# PCB_with_nRF_SINGLE.net
KiCad netlist of a schematic drawn in EAGLE
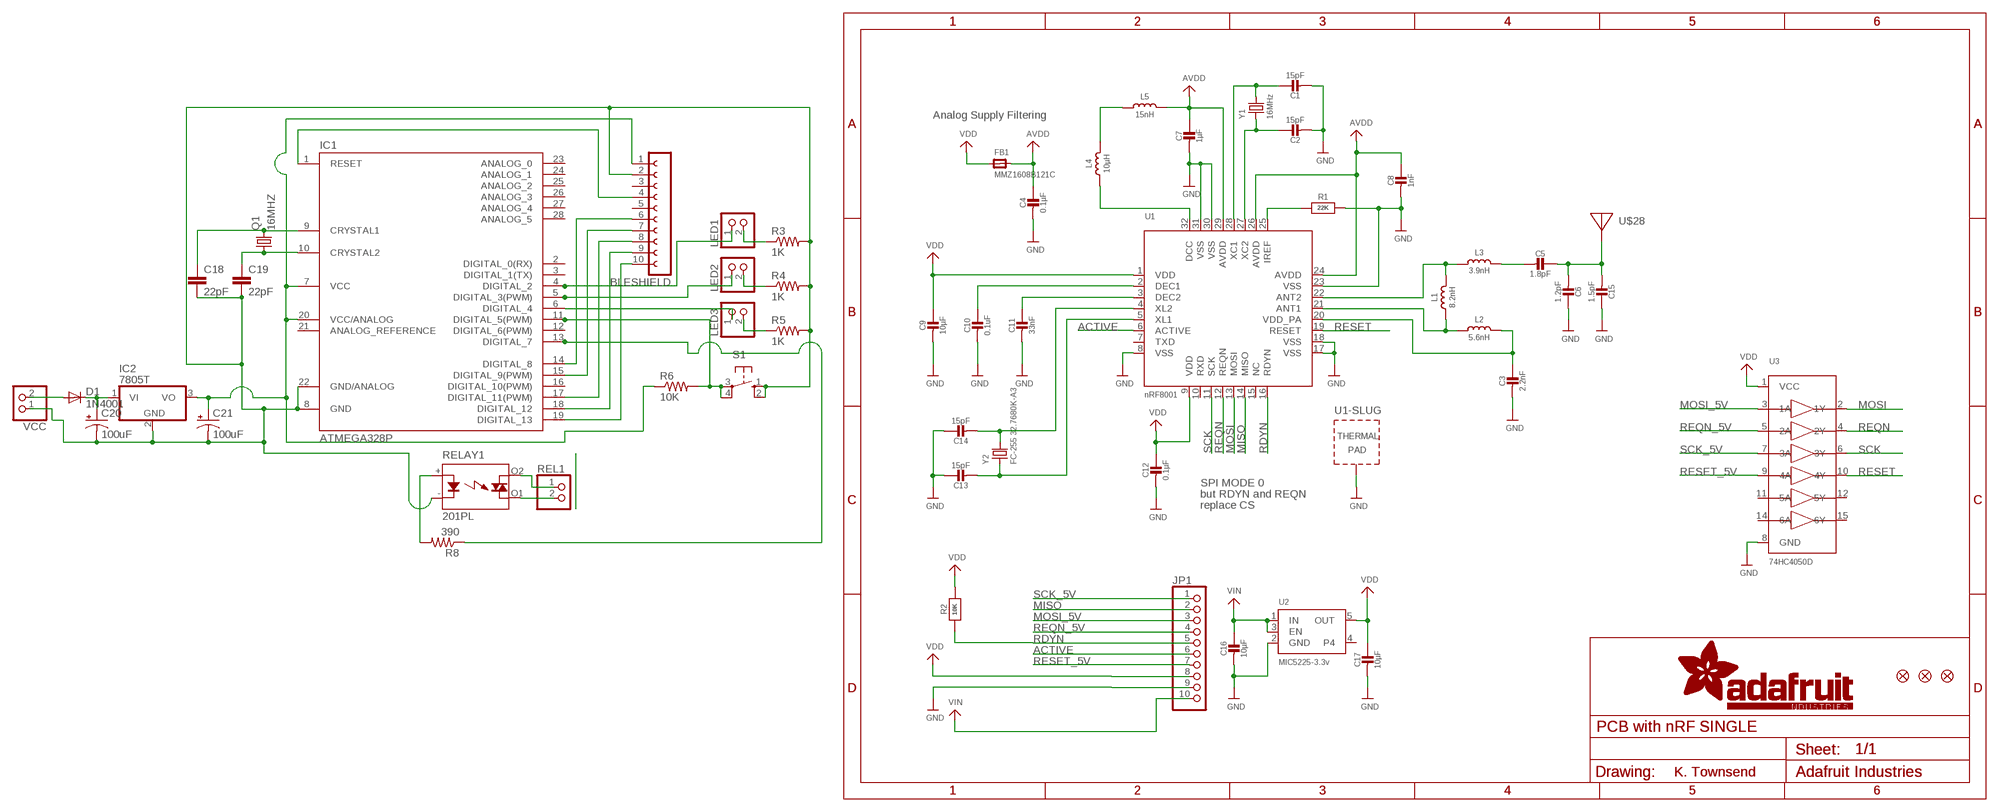
[diagram p0: schematic, sheet 1]

(export (version "E")
  (design (tool "Eeschema 10.0.6"))
  (components
    (comp (ref "BLESHIELD")
      (value "FE10-1")
      (footprint "eagle-import:FE10")
      (libsource (lib "eagle-import") (part "FE10-1"))
    )
    (comp (ref "C1")
      (value "15pF")
      (footprint "eagle-import:0805-NO")
      (libsource (lib "eagle-import") (part "CAP_CERAMIC0805-NOOUTLINE"))
    )
    (comp (ref "C2")
      (value "15pF")
      (footprint "eagle-import:0805-NO")
      (libsource (lib "eagle-import") (part "CAP_CERAMIC0805-NOOUTLINE"))
    )
    (comp (ref "C3")
      (value "2.2nF")
      (footprint "eagle-import:_0402")
      (libsource (lib "eagle-import") (part "CAP_CERAMIC_0402"))
    )
    (comp (ref "C4")
      (value "0.1µF")
      (footprint "eagle-import:0805-NO")
      (libsource (lib "eagle-import") (part "CAP_CERAMIC0805-NOOUTLINE"))
    )
    (comp (ref "C5")
      (value "1.8pF")
      (footprint "eagle-import:_0402MP")
      (libsource (lib "eagle-import") (part "CAP_CERAMIC_0402MP"))
    )
    (comp (ref "C6")
      (value "1.2pF")
      (footprint "eagle-import:_0402MP")
      (libsource (lib "eagle-import") (part "CAP_CERAMIC_0402MP"))
    )
    (comp (ref "C7")
      (value "1µF")
      (footprint "eagle-import:0805-NO")
      (libsource (lib "eagle-import") (part "CAP_CERAMIC0805-NOOUTLINE"))
    )
    (comp (ref "C8")
      (value "1nF")
      (footprint "eagle-import:_0603")
      (libsource (lib "eagle-import") (part "CAP_CERAMIC_0603"))
    )
    (comp (ref "C9")
      (value "10µF")
      (footprint "eagle-import:0805-NO")
      (libsource (lib "eagle-import") (part "CAP_CERAMIC0805-NOOUTLINE"))
    )
    (comp (ref "C10")
      (value "0.1uF")
      (footprint "eagle-import:0805-NO")
      (libsource (lib "eagle-import") (part "CAP_CERAMIC0805-NOOUTLINE"))
    )
    (comp (ref "C11")
      (value "33nF")
      (footprint "eagle-import:0805-NO")
      (libsource (lib "eagle-import") (part "CAP_CERAMIC0805-NOOUTLINE"))
    )
    (comp (ref "C12")
      (value "0.1µF")
      (footprint "eagle-import:0805-NO")
      (libsource (lib "eagle-import") (part "CAP_CERAMIC0805-NOOUTLINE"))
    )
    (comp (ref "C13")
      (value "15pF")
      (footprint "eagle-import:0805-NO")
      (libsource (lib "eagle-import") (part "CAP_CERAMIC0805-NOOUTLINE"))
    )
    (comp (ref "C14")
      (value "15pF")
      (footprint "eagle-import:0805-NO")
      (libsource (lib "eagle-import") (part "CAP_CERAMIC0805-NOOUTLINE"))
    )
    (comp (ref "C15")
      (value "1.5pF")
      (footprint "eagle-import:_0402MP")
      (libsource (lib "eagle-import") (part "CAP_CERAMIC_0402MP"))
    )
    (comp (ref "C16")
      (value "10µF")
      (footprint "eagle-import:0805-NO")
      (libsource (lib "eagle-import") (part "CAP_CERAMIC0805-NOOUTLINE"))
    )
    (comp (ref "C17")
      (value "10µF")
      (footprint "eagle-import:0805-NO")
      (libsource (lib "eagle-import") (part "CAP_CERAMIC0805-NOOUTLINE"))
    )
    (comp (ref "C18")
      (value "22pF")
      (footprint "eagle-import:C025-030X050")
      (libsource (lib "eagle-import") (part "C-EU025-030X050"))
    )
    (comp (ref "C19")
      (value "22pF")
      (footprint "eagle-import:C025-030X050")
      (libsource (lib "eagle-import") (part "C-EU025-030X050"))
    )
    (comp (ref "C20")
      (value "100uF")
      (footprint "eagle-import:E2,5-6")
      (libsource (lib "eagle-import") (part "CPOL-USE2.5-6"))
    )
    (comp (ref "C21")
      (value "100uF")
      (footprint "eagle-import:E2,5-6")
      (libsource (lib "eagle-import") (part "CPOL-USE2.5-6"))
    )
    (comp (ref "D1")
      (value "1N4001")
      (footprint "eagle-import:DO41-10")
      (libsource (lib "eagle-import") (part "1N4004"))
    )
    (comp (ref "FB1")
      (value "MMZ1608B121C")
      (footprint "eagle-import:0805")
      (libsource (lib "eagle-import") (part "FERRITE0805"))
    )
    (comp (ref "FID1")
      (value "FIDUCIAL\"\"")
      (footprint "eagle-import:FIDUCIAL_1MM")
      (libsource (lib "eagle-import") (part "FIDUCIAL{dblquote}{dblquote}"))
    )
    (comp (ref "FID2")
      (value "FIDUCIAL\"\"")
      (footprint "eagle-import:FIDUCIAL_1MM")
      (libsource (lib "eagle-import") (part "FIDUCIAL{dblquote}{dblquote}"))
    )
    (comp (ref "FID3")
      (value "FIDUCIAL\"\"")
      (footprint "eagle-import:FIDUCIAL_1MM")
      (fields (field (name "BOM") "EXCLUDE"))
      (libsource (lib "eagle-import") (part "FIDUCIAL{dblquote}{dblquote}"))
    )
    (comp (ref "IC1")
      (value "ATMEGA328P")
      (footprint "eagle-import:DIL28-3")
      (libsource (lib "eagle-import") (part "ATMEGA168-PU"))
    )
    (comp (ref "IC2")
      (value "7805T")
      (footprint "eagle-import:TO220H")
      (libsource (lib "eagle-import") (part "78T05"))
    )
    (comp (ref "JP1")
      (value "HEADER-1X1070MIL")
      (footprint "eagle-import:1X10_ROUND70")
      (libsource (lib "eagle-import") (part "HEADER-1X1070MIL"))
    )
    (comp (ref "L1")
      (value "8.2nH")
      (footprint "eagle-import:_0402")
      (libsource (lib "eagle-import") (part "INDUCTOR_0402"))
    )
    (comp (ref "L2")
      (value "5.6nH")
      (footprint "eagle-import:_0402")
      (libsource (lib "eagle-import") (part "INDUCTOR_0402"))
    )
    (comp (ref "L3")
      (value "3.9nH")
      (footprint "eagle-import:_0402")
      (libsource (lib "eagle-import") (part "INDUCTOR_0402"))
    )
    (comp (ref "L4")
      (value "10µH")
      (footprint "eagle-import:_0603")
      (libsource (lib "eagle-import") (part "INDUCTOR_0603"))
    )
    (comp (ref "L5")
      (value "15nH")
      (footprint "eagle-import:_0603")
      (libsource (lib "eagle-import") (part "INDUCTOR_0603"))
    )
    (comp (ref "LED1")
      (value "PINHD-1X2")
      (footprint "eagle-import:1X02")
      (libsource (lib "eagle-import") (part "PINHD-1X2"))
    )
    (comp (ref "LED2")
      (value "PINHD-1X2")
      (footprint "eagle-import:1X02")
      (libsource (lib "eagle-import") (part "PINHD-1X2"))
    )
    (comp (ref "LED3")
      (value "PINHD-1X2")
      (footprint "eagle-import:1X02")
      (libsource (lib "eagle-import") (part "PINHD-1X2"))
    )
    (comp (ref "Q1")
      (value "16MHZ")
      (footprint "eagle-import:HC49_S")
      (libsource (lib "eagle-import") (part "CRYSTALHC49S"))
    )
    (comp (ref "R1")
      (value "22K")
      (footprint "eagle-import:_0805MP")
      (libsource (lib "eagle-import") (part "RESISTOR_0805MP"))
    )
    (comp (ref "R2")
      (value "10K")
      (footprint "eagle-import:0805-NO")
      (libsource (lib "eagle-import") (part "RESISTOR0805_NOOUTLINE"))
    )
    (comp (ref "R3")
      (value "1K")
      (footprint "eagle-import:0204_5")
      (libsource (lib "eagle-import") (part "R-US_0204/5"))
    )
    (comp (ref "R4")
      (value "1K")
      (footprint "eagle-import:0204_5")
      (libsource (lib "eagle-import") (part "R-US_0204/5"))
    )
    (comp (ref "R5")
      (value "1K")
      (footprint "eagle-import:0204_5")
      (libsource (lib "eagle-import") (part "R-US_0204/5"))
    )
    (comp (ref "R6")
      (value "10K")
      (footprint "eagle-import:0204_5")
      (libsource (lib "eagle-import") (part "R-US_0204/5"))
    )
    (comp (ref "R8")
      (value "390")
      (footprint "eagle-import:0204_5")
      (libsource (lib "eagle-import") (part "R-US_0204/5"))
    )
    (comp (ref "REL1")
      (value "PINHD-1X2")
      (footprint "eagle-import:1X02")
      (libsource (lib "eagle-import") (part "PINHD-1X2"))
    )
    (comp (ref "RELAY1")
      (value "201PL")
      (footprint "eagle-import:AQG")
      (fields (field (name "MF") "AROMAT/ MATSUSHITA") (field (name "MPN") "AQG12105"))
      (libsource (lib "eagle-import") (part "AQG12105"))
    )
    (comp (ref "S1")
      (value "10-XX")
      (footprint "eagle-import:B3F-10XX")
      (fields (field (name "MPN") "B3F-1000"))
      (libsource (lib "eagle-import") (part "10-XX"))
    )
    (comp (ref "U$28")
      (value "ANTENNA_PCBNRF8001_1.6MM")
      (footprint "eagle-import:ANT_PCB_2.4GHZ_NRF8001_1.6MM_1OZ")
      (libsource (lib "eagle-import") (part "ANTENNA_PCBNRF8001_1.6MM"))
    )
    (comp (ref "U1")
      (value "nRF8001")
      (footprint "eagle-import:QFN32_5MM")
      (libsource (lib "eagle-import") (part "NRF8001"))
    )
    (comp (ref "U2")
      (value "MIC5225-3.3v")
      (footprint "eagle-import:SOT23-5")
      (libsource (lib "eagle-import") (part "VREG_SOT23-5"))
    )
    (comp (ref "U3")
      (value "74HC4050D")
      (footprint "eagle-import:TSSOP16")
      (libsource (lib "eagle-import") (part "74HC4050DTSSOP"))
    )
    (comp (ref "VCC")
      (value "PINHD-1X2")
      (footprint "eagle-import:1X02")
      (libsource (lib "eagle-import") (part "PINHD-1X2"))
    )
    (comp (ref "Y1")
      (value "16MHz")
      (footprint "eagle-import:CRYSTAL_2.5X2")
      (libsource (lib "eagle-import") (part "CRYSTAL2.5X2.0"))
    )
    (comp (ref "Y2")
      (value "FC-255 32.7680K-A3")
      (footprint "eagle-import:CRYSTAL_4.9X1.8")
      (libsource (lib "eagle-import") (part "CRYSTAL4.9X1.8"))
    )
  )
  (nets
    (net (code "1") (name "/ACTIVE") (class "Default")
      (node (ref "JP1") (pin "6") (pinfunction "6_6") (pintype "passive"))
      (node (ref "U1") (pin "6") (pinfunction "ACTIVE_6") (pintype "output"))
    )
    (net (code "2") (name "/MISO") (class "Default")
      (node (ref "JP1") (pin "2") (pinfunction "2_2") (pintype "passive"))
      (node (ref "U1") (pin "14") (pinfunction "MISO_14") (pintype "output"))
    )
    (net (code "3") (name "/MOSI") (class "Default")
      (node (ref "U1") (pin "13") (pinfunction "MOSI_13") (pintype "input"))
      (node (ref "U3") (pin "2") (pinfunction "1Y_2") (pintype "bidirectional"))
    )
    (net (code "4") (name "/MOSI_5V") (class "Default")
      (node (ref "JP1") (pin "3") (pinfunction "3_3") (pintype "passive"))
      (node (ref "U3") (pin "3") (pinfunction "1A_3") (pintype "bidirectional"))
    )
    (net (code "5") (name "/RDYN") (class "Default")
      (node (ref "JP1") (pin "5") (pinfunction "5_5") (pintype "passive"))
      (node (ref "R2") (pin "1") (pinfunction "1_1") (pintype "passive"))
      (node (ref "U1") (pin "16") (pinfunction "RDYN_16") (pintype "output"))
    )
    (net (code "6") (name "/REQN") (class "Default")
      (node (ref "U1") (pin "12") (pinfunction "REQN_12") (pintype "input"))
      (node (ref "U3") (pin "4") (pinfunction "2Y_4") (pintype "bidirectional"))
    )
    (net (code "7") (name "/REQN_5V") (class "Default")
      (node (ref "JP1") (pin "4") (pinfunction "4_4") (pintype "passive"))
      (node (ref "U3") (pin "5") (pinfunction "2A_5") (pintype "bidirectional"))
    )
    (net (code "8") (name "/RESET") (class "Default")
      (node (ref "U1") (pin "19") (pinfunction "RESET_19") (pintype "input"))
      (node (ref "U3") (pin "10") (pinfunction "4Y_10") (pintype "bidirectional"))
    )
    (net (code "9") (name "/RESET_5V") (class "Default")
      (node (ref "JP1") (pin "7") (pinfunction "7_7") (pintype "passive"))
      (node (ref "U3") (pin "9") (pinfunction "4A_9") (pintype "bidirectional"))
    )
    (net (code "10") (name "/SCK") (class "Default")
      (node (ref "U1") (pin "11") (pinfunction "SCK_11") (pintype "input"))
      (node (ref "U3") (pin "6") (pinfunction "3Y_6") (pintype "bidirectional"))
    )
    (net (code "11") (name "/SCK_5V") (class "Default")
      (node (ref "JP1") (pin "1") (pinfunction "1_1") (pintype "passive"))
      (node (ref "U3") (pin "7") (pinfunction "3A_7") (pintype "bidirectional"))
    )
    (net (code "12") (name "AVDD") (class "Default")
      (node (ref "C4") (pin "1") (pinfunction "1_1") (pintype "passive"))
      (node (ref "C7") (pin "1") (pinfunction "1_1") (pintype "passive"))
      (node (ref "C8") (pin "1") (pinfunction "1_1") (pintype "passive"))
      (node (ref "FB1") (pin "2") (pinfunction "P$2_2") (pintype "passive"))
      (node (ref "L5") (pin "2") (pinfunction "2_2") (pintype "passive"))
      (node (ref "U1") (pin "24") (pinfunction "AVDD_24") (pintype "power_in"))
      (node (ref "U1") (pin "26") (pinfunction "AVDD_26") (pintype "power_in"))
      (node (ref "U1") (pin "29") (pinfunction "AVDD_29") (pintype "power_in"))
    )
    (net (code "13") (name "GND") (class "Default")
      (node (ref "C1") (pin "2") (pinfunction "2_2") (pintype "passive"))
      (node (ref "C10") (pin "2") (pinfunction "2_2") (pintype "passive"))
      (node (ref "C11") (pin "2") (pinfunction "2_2") (pintype "passive"))
      (node (ref "C12") (pin "2") (pinfunction "2_2") (pintype "passive"))
      (node (ref "C13") (pin "1") (pinfunction "1_1") (pintype "passive"))
      (node (ref "C14") (pin "1") (pinfunction "1_1") (pintype "passive"))
      (node (ref "C15") (pin "1") (pinfunction "1_1") (pintype "passive"))
      (node (ref "C16") (pin "2") (pinfunction "2_2") (pintype "passive"))
      (node (ref "C17") (pin "2") (pinfunction "2_2") (pintype "passive"))
      (node (ref "C2") (pin "2") (pinfunction "2_2") (pintype "passive"))
      (node (ref "C3") (pin "2") (pinfunction "2_2") (pintype "passive"))
      (node (ref "C4") (pin "2") (pinfunction "2_2") (pintype "passive"))
      (node (ref "C6") (pin "1") (pinfunction "1_1") (pintype "passive"))
      (node (ref "C7") (pin "2") (pinfunction "2_2") (pintype "passive"))
      (node (ref "C8") (pin "2") (pinfunction "2_2") (pintype "passive"))
      (node (ref "C9") (pin "2") (pinfunction "2_2") (pintype "passive"))
      (node (ref "JP1") (pin "9") (pinfunction "9_9") (pintype "passive"))
      (node (ref "R1") (pin "2") (pinfunction "2_2") (pintype "passive"))
      (node (ref "U1") (pin "17") (pinfunction "VSS_17") (pintype "power_in"))
      (node (ref "U1") (pin "18") (pinfunction "VSS_18") (pintype "power_in"))
      (node (ref "U1") (pin "23") (pinfunction "VSS_23") (pintype "power_in"))
      (node (ref "U1") (pin "30") (pinfunction "VSS_30") (pintype "power_in"))
      (node (ref "U1") (pin "31") (pinfunction "VSS_31") (pintype "power_in"))
      (node (ref "U1") (pin "33") (pinfunction "TP_33") (pintype "power_in"))
      (node (ref "U1") (pin "8") (pinfunction "VSS_8") (pintype "power_in"))
      (node (ref "U2") (pin "2") (pinfunction "GND_2") (pintype "power_in"))
      (node (ref "U3") (pin "8") (pinfunction "GND_8") (pintype "bidirectional"))
    )
    (net (code "14") (name "Net-(C5-Pad2)") (class "Default")
      (node (ref "C5") (pin "2") (pinfunction "2_2") (pintype "passive"))
      (node (ref "L3") (pin "2") (pinfunction "2_2") (pintype "passive"))
    )
    (net (code "15") (name "Net-(D1-PadA)") (class "Default")
      (node (ref "D1") (pin "A") (pinfunction "A_A") (pintype "passive"))
      (node (ref "VCC") (pin "2") (pinfunction "2_2") (pintype "passive"))
    )
    (net (code "16") (name "Net-(IC1-CRYSTAL1)") (class "Default")
      (node (ref "C18") (pin "1") (pinfunction "1_1") (pintype "passive"))
      (node (ref "IC1") (pin "9") (pinfunction "CRYSTAL1_9") (pintype "bidirectional"))
      (node (ref "Q1") (pin "2") (pinfunction "2_2") (pintype "passive"))
    )
    (net (code "17") (name "Net-(IC1-CRYSTAL2)") (class "Default")
      (node (ref "C19") (pin "1") (pinfunction "1_1") (pintype "passive"))
      (node (ref "IC1") (pin "10") (pinfunction "CRYSTAL2_10") (pintype "bidirectional"))
      (node (ref "Q1") (pin "1") (pinfunction "1_1") (pintype "passive"))
    )
    (net (code "18") (name "Net-(IC1-DIGITAL_2)") (class "Default")
      (node (ref "IC1") (pin "4") (pinfunction "DIGITAL_2_4") (pintype "bidirectional"))
      (node (ref "LED1") (pin "1") (pinfunction "1_1") (pintype "passive"))
    )
    (net (code "19") (name "Net-(IC1-DIGITAL_3(PWM))") (class "Default")
      (node (ref "IC1") (pin "5") (pinfunction "DIGITAL_3(PWM)_5") (pintype "bidirectional"))
      (node (ref "LED2") (pin "1") (pinfunction "1_1") (pintype "passive"))
    )
    (net (code "20") (name "Net-(IC1-DIGITAL_4)") (class "Default")
      (node (ref "IC1") (pin "6") (pinfunction "DIGITAL_4_6") (pintype "bidirectional"))
      (node (ref "LED3") (pin "1") (pinfunction "1_1") (pintype "passive"))
    )
    (net (code "21") (name "Net-(IC1-DIGITAL_5(PWM))") (class "Default")
      (node (ref "IC1") (pin "11") (pinfunction "DIGITAL_5(PWM)_11") (pintype "bidirectional"))
      (node (ref "R6") (pin "2") (pinfunction "2_2") (pintype "passive"))
      (node (ref "S1") (pin "3") (pinfunction "P_3") (pintype "passive"))
      (node (ref "S1") (pin "4") (pinfunction "P1_4") (pintype "passive"))
    )
    (net (code "22") (name "Net-(IC1-DIGITAL_7)") (class "Default")
      (node (ref "IC1") (pin "13") (pinfunction "DIGITAL_7_13") (pintype "bidirectional"))
      (node (ref "R8") (pin "1") (pinfunction "1_1") (pintype "passive"))
    )
    (net (code "23") (name "Net-(IC1-DIGITAL_8)") (class "Default")
      (node (ref "BLESHIELD") (pin "6") (pinfunction "6_6") (pintype "passive"))
      (node (ref "IC1") (pin "14") (pinfunction "DIGITAL_8_14") (pintype "bidirectional"))
    )
    (net (code "24") (name "Net-(IC1-DIGITAL_9(PWM))") (class "Default")
      (node (ref "BLESHIELD") (pin "7") (pinfunction "7_7") (pintype "passive"))
      (node (ref "IC1") (pin "15") (pinfunction "DIGITAL_9(PWM)_15") (pintype "bidirectional"))
    )
    (net (code "25") (name "Net-(IC1-DIGITAL_11(PWM))") (class "Default")
      (node (ref "BLESHIELD") (pin "8") (pinfunction "8_8") (pintype "passive"))
      (node (ref "IC1") (pin "17") (pinfunction "DIGITAL_11(PWM)_17") (pintype "bidirectional"))
    )
    (net (code "26") (name "Net-(IC1-DIGITAL_12)") (class "Default")
      (node (ref "BLESHIELD") (pin "9") (pinfunction "9_9") (pintype "passive"))
      (node (ref "IC1") (pin "18") (pinfunction "DIGITAL_12_18") (pintype "bidirectional"))
    )
    (net (code "27") (name "Net-(IC1-DIGITAL_13)") (class "Default")
      (node (ref "BLESHIELD") (pin "10") (pinfunction "10_10") (pintype "passive"))
      (node (ref "IC1") (pin "19") (pinfunction "DIGITAL_13_19") (pintype "bidirectional"))
    )
    (net (code "28") (name "Net-(IC1-GND)") (class "Default")
      (node (ref "BLESHIELD") (pin "2") (pinfunction "2_2") (pintype "passive"))
      (node (ref "C18") (pin "2") (pinfunction "2_2") (pintype "passive"))
      (node (ref "C19") (pin "2") (pinfunction "2_2") (pintype "passive"))
      (node (ref "C20") (pin "-") (pinfunction "-_-") (pintype "passive"))
      (node (ref "C21") (pin "-") (pinfunction "-_-") (pintype "passive"))
      (node (ref "IC1") (pin "22") (pinfunction "GND/ANALOG_22") (pintype "power_in"))
      (node (ref "IC1") (pin "8") (pinfunction "GND_8") (pintype "power_in"))
      (node (ref "IC2") (pin "2") (pinfunction "GND_2") (pintype "passive"))
      (node (ref "R3") (pin "2") (pinfunction "2_2") (pintype "passive"))
      (node (ref "R4") (pin "2") (pinfunction "2_2") (pintype "passive"))
      (node (ref "R5") (pin "2") (pinfunction "2_2") (pintype "passive"))
      (node (ref "RELAY1") (pin "-") (pinfunction "K_-") (pintype "passive"))
      (node (ref "S1") (pin "1") (pinfunction "S_1") (pintype "passive"))
      (node (ref "S1") (pin "2") (pinfunction "S1_2") (pintype "passive"))
      (node (ref "VCC") (pin "1") (pinfunction "1_1") (pintype "passive"))
    )
    (net (code "29") (name "Net-(IC1-RESET)") (class "Default")
      (node (ref "BLESHIELD") (pin "4") (pinfunction "4_4") (pintype "passive"))
      (node (ref "IC1") (pin "1") (pinfunction "RESET_1") (pintype "bidirectional"))
    )
    (net (code "30") (name "Net-(IC1-VCC)") (class "Default")
      (node (ref "BLESHIELD") (pin "1") (pinfunction "1_1") (pintype "passive"))
      (node (ref "C21") (pin "+") (pinfunction "+_+") (pintype "passive"))
      (node (ref "IC1") (pin "20") (pinfunction "VCC/ANALOG_20") (pintype "passive"))
      (node (ref "IC1") (pin "7") (pinfunction "VCC_7") (pintype "power_in"))
      (node (ref "IC2") (pin "3") (pinfunction "VO_3") (pintype "passive"))
      (node (ref "R6") (pin "1") (pinfunction "1_1") (pintype "passive"))
    )
    (net (code "31") (name "Net-(IC2-VI)") (class "Default")
      (node (ref "C20") (pin "+") (pinfunction "+_+") (pintype "passive"))
      (node (ref "D1") (pin "C") (pinfunction "C_C") (pintype "passive"))
      (node (ref "IC2") (pin "1") (pinfunction "VI_1") (pintype "input"))
    )
    (net (code "32") (name "Net-(L4-Pad2)") (class "Default")
      (node (ref "L4") (pin "2") (pinfunction "2_2") (pintype "passive"))
      (node (ref "L5") (pin "1") (pinfunction "1_1") (pintype "passive"))
    )
    (net (code "33") (name "Net-(LED1-Pad2)") (class "Default")
      (node (ref "LED1") (pin "2") (pinfunction "2_2") (pintype "passive"))
      (node (ref "R3") (pin "1") (pinfunction "1_1") (pintype "passive"))
    )
    (net (code "34") (name "Net-(LED2-Pad2)") (class "Default")
      (node (ref "LED2") (pin "2") (pinfunction "2_2") (pintype "passive"))
      (node (ref "R4") (pin "1") (pinfunction "1_1") (pintype "passive"))
    )
    (net (code "35") (name "Net-(LED3-Pad2)") (class "Default")
      (node (ref "LED3") (pin "2") (pinfunction "2_2") (pintype "passive"))
      (node (ref "R5") (pin "1") (pinfunction "1_1") (pintype "passive"))
    )
    (net (code "36") (name "Net-(RELAY1-A)") (class "Default")
      (node (ref "R8") (pin "2") (pinfunction "2_2") (pintype "passive"))
      (node (ref "RELAY1") (pin "+") (pinfunction "A_+") (pintype "passive"))
    )
    (net (code "37") (name "Net-(RELAY1-DS1)") (class "Default")
      (node (ref "REL1") (pin "1") (pinfunction "1_1") (pintype "passive"))
      (node (ref "RELAY1") (pin "O2") (pinfunction "DS1_O2") (pintype "passive"))
    )
    (net (code "38") (name "Net-(RELAY1-DS2)") (class "Default")
      (node (ref "REL1") (pin "2") (pinfunction "2_2") (pintype "passive"))
      (node (ref "RELAY1") (pin "O1") (pinfunction "DS2_O1") (pintype "passive"))
    )
    (net (code "39") (name "Net-(U$28-P$1)") (class "Default")
      (node (ref "C15") (pin "2") (pinfunction "2_2") (pintype "passive"))
      (node (ref "C5") (pin "1") (pinfunction "1_1") (pintype "passive"))
      (node (ref "C6") (pin "2") (pinfunction "2_2") (pintype "passive"))
      (node (ref "U$28") (pin "FEED") (pinfunction "P$1_FEED") (pintype "passive"))
    )
    (net (code "40") (name "Net-(U1B-ANT1)") (class "Default")
      (node (ref "L1") (pin "1") (pinfunction "1_1") (pintype "passive"))
      (node (ref "L2") (pin "1") (pinfunction "1_1") (pintype "passive"))
      (node (ref "U1") (pin "21") (pinfunction "ANT1_21") (pintype "bidirectional"))
    )
    (net (code "41") (name "Net-(U1B-ANT2)") (class "Default")
      (node (ref "L1") (pin "2") (pinfunction "2_2") (pintype "passive"))
      (node (ref "L3") (pin "1") (pinfunction "1_1") (pintype "passive"))
      (node (ref "U1") (pin "22") (pinfunction "ANT2_22") (pintype "bidirectional"))
    )
    (net (code "42") (name "Net-(U1B-DCC)") (class "Default")
      (node (ref "L4") (pin "1") (pinfunction "1_1") (pintype "passive"))
      (node (ref "U1") (pin "32") (pinfunction "DCC_32") (pintype "bidirectional"))
    )
    (net (code "43") (name "Net-(U1B-DEC1)") (class "Default")
      (node (ref "C10") (pin "1") (pinfunction "1_1") (pintype "passive"))
      (node (ref "U1") (pin "2") (pinfunction "DEC1_2") (pintype "bidirectional"))
    )
    (net (code "44") (name "Net-(U1B-DEC2)") (class "Default")
      (node (ref "C11") (pin "1") (pinfunction "1_1") (pintype "passive"))
      (node (ref "U1") (pin "3") (pinfunction "DEC2_3") (pintype "bidirectional"))
    )
    (net (code "45") (name "Net-(U1B-IREF)") (class "Default")
      (node (ref "R1") (pin "1") (pinfunction "1_1") (pintype "passive"))
      (node (ref "U1") (pin "25") (pinfunction "IREF_25") (pintype "output"))
    )
    (net (code "46") (name "Net-(U1B-VDD_PA)") (class "Default")
      (node (ref "C3") (pin "1") (pinfunction "1_1") (pintype "passive"))
      (node (ref "L2") (pin "2") (pinfunction "2_2") (pintype "passive"))
      (node (ref "U1") (pin "20") (pinfunction "VDD_PA_20") (pintype "bidirectional"))
    )
    (net (code "47") (name "Net-(U1B-XC1)") (class "Default")
      (node (ref "C1") (pin "1") (pinfunction "1_1") (pintype "passive"))
      (node (ref "U1") (pin "28") (pinfunction "XC1_28") (pintype "input"))
      (node (ref "Y1") (pin "3") (pinfunction "2_3") (pintype "passive"))
    )
    (net (code "48") (name "Net-(U1B-XC2)") (class "Default")
      (node (ref "C2") (pin "1") (pinfunction "1_1") (pintype "passive"))
      (node (ref "U1") (pin "27") (pinfunction "XC2_27") (pintype "output"))
      (node (ref "Y1") (pin "1") (pinfunction "1_1") (pintype "passive"))
    )
    (net (code "49") (name "Net-(U1B-XL1)") (class "Default")
      (node (ref "C13") (pin "2") (pinfunction "2_2") (pintype "passive"))
      (node (ref "U1") (pin "5") (pinfunction "XL1_5") (pintype "input"))
      (node (ref "Y2") (pin "1") (pinfunction "1_1") (pintype "passive"))
    )
    (net (code "50") (name "Net-(U1B-XL2)") (class "Default")
      (node (ref "C14") (pin "2") (pinfunction "2_2") (pintype "passive"))
      (node (ref "U1") (pin "4") (pinfunction "XL2_4") (pintype "output"))
      (node (ref "Y2") (pin "2") (pinfunction "2_2") (pintype "passive"))
    )
    (net (code "51") (name "VDD") (class "Default")
      (node (ref "C12") (pin "1") (pinfunction "1_1") (pintype "passive"))
      (node (ref "C17") (pin "1") (pinfunction "1_1") (pintype "passive"))
      (node (ref "C9") (pin "1") (pinfunction "1_1") (pintype "passive"))
      (node (ref "FB1") (pin "1") (pinfunction "P$1_1") (pintype "passive"))
      (node (ref "JP1") (pin "8") (pinfunction "8_8") (pintype "passive"))
      (node (ref "R2") (pin "2") (pinfunction "2_2") (pintype "passive"))
      (node (ref "U1") (pin "1") (pinfunction "VDD_1") (pintype "power_in"))
      (node (ref "U1") (pin "9") (pinfunction "VDD_9") (pintype "power_in"))
      (node (ref "U2") (pin "5") (pinfunction "OUT_5") (pintype "power_in"))
      (node (ref "U3") (pin "1") (pinfunction "VCC_1") (pintype "bidirectional"))
    )
    (net (code "52") (name "VIN") (class "Default")
      (node (ref "C16") (pin "1") (pinfunction "1_1") (pintype "passive"))
      (node (ref "JP1") (pin "10") (pinfunction "10_10") (pintype "passive"))
      (node (ref "U2") (pin "1") (pinfunction "IN_1") (pintype "power_in"))
      (node (ref "U2") (pin "3") (pinfunction "EN_3") (pintype "input"))
    )
    (net (code "53") (name "unconnected-(BLESHIELD-Pad3)") (class "Default")
      (node (ref "BLESHIELD") (pin "3") (pinfunction "3_3") (pintype "passive"))
    )
    (net (code "54") (name "unconnected-(BLESHIELD-Pad5)") (class "Default")
      (node (ref "BLESHIELD") (pin "5") (pinfunction "5_5") (pintype "passive"))
    )
    (net (code "55") (name "unconnected-(IC1-ANALOG_0-Pad23)") (class "Default")
      (node (ref "IC1") (pin "23") (pinfunction "ANALOG_0_23") (pintype "bidirectional"))
    )
    (net (code "56") (name "unconnected-(IC1-ANALOG_1-Pad24)") (class "Default")
      (node (ref "IC1") (pin "24") (pinfunction "ANALOG_1_24") (pintype "bidirectional"))
    )
    (net (code "57") (name "unconnected-(IC1-ANALOG_2-Pad25)") (class "Default")
      (node (ref "IC1") (pin "25") (pinfunction "ANALOG_2_25") (pintype "bidirectional"))
    )
    (net (code "58") (name "unconnected-(IC1-ANALOG_3-Pad26)") (class "Default")
      (node (ref "IC1") (pin "26") (pinfunction "ANALOG_3_26") (pintype "bidirectional"))
    )
    (net (code "59") (name "unconnected-(IC1-ANALOG_4-Pad27)") (class "Default")
      (node (ref "IC1") (pin "27") (pinfunction "ANALOG_4_27") (pintype "bidirectional"))
    )
    (net (code "60") (name "unconnected-(IC1-ANALOG_5-Pad28)") (class "Default")
      (node (ref "IC1") (pin "28") (pinfunction "ANALOG_5_28") (pintype "bidirectional"))
    )
    (net (code "61") (name "unconnected-(IC1-ANALOG_REFERENCE-Pad21)") (class "Default")
      (node (ref "IC1") (pin "21") (pinfunction "ANALOG_REFERENCE_21") (pintype "passive"))
    )
    (net (code "62") (name "unconnected-(IC1-DIGITAL_0(RX)-Pad2)") (class "Default")
      (node (ref "IC1") (pin "2") (pinfunction "DIGITAL_0(RX)_2") (pintype "bidirectional"))
    )
    (net (code "63") (name "unconnected-(IC1-DIGITAL_1(TX)-Pad3)") (class "Default")
      (node (ref "IC1") (pin "3") (pinfunction "DIGITAL_1(TX)_3") (pintype "bidirectional"))
    )
    (net (code "64") (name "unconnected-(IC1-DIGITAL_6(PWM)-Pad12)") (class "Default")
      (node (ref "IC1") (pin "12") (pinfunction "DIGITAL_6(PWM)_12") (pintype "bidirectional"))
    )
    (net (code "65") (name "unconnected-(IC1-DIGITAL_10(PWM)-Pad16)") (class "Default")
      (node (ref "IC1") (pin "16") (pinfunction "DIGITAL_10(PWM)_16") (pintype "bidirectional"))
    )
    (net (code "66") (name "unconnected-(U1B-NC-Pad15)") (class "Default")
      (node (ref "U1") (pin "15") (pinfunction "NC_15") (pintype "no_connect"))
    )
    (net (code "67") (name "unconnected-(U1B-RXD-Pad10)") (class "Default")
      (node (ref "U1") (pin "10") (pinfunction "RXD_10") (pintype "input"))
    )
    (net (code "68") (name "unconnected-(U1B-TXD-Pad7)") (class "Default")
      (node (ref "U1") (pin "7") (pinfunction "TXD_7") (pintype "output"))
    )
    (net (code "69") (name "unconnected-(U2-P4-Pad4)") (class "Default")
      (node (ref "U2") (pin "4") (pinfunction "P4_4") (pintype "bidirectional"))
    )
    (net (code "70") (name "unconnected-(U3-5A-Pad11)") (class "Default")
      (node (ref "U3") (pin "11") (pinfunction "5A_11") (pintype "bidirectional"))
    )
    (net (code "71") (name "unconnected-(U3-5Y-Pad12)") (class "Default")
      (node (ref "U3") (pin "12") (pinfunction "5Y_12") (pintype "bidirectional"))
    )
    (net (code "72") (name "unconnected-(U3-6A-Pad14)") (class "Default")
      (node (ref "U3") (pin "14") (pinfunction "6A_14") (pintype "bidirectional"))
    )
    (net (code "73") (name "unconnected-(U3-6Y-Pad15)") (class "Default")
      (node (ref "U3") (pin "15") (pinfunction "6Y_15") (pintype "bidirectional"))
    )
  )
)
